# d1.net
KiCad netlist of a schematic drawn in EAGLE
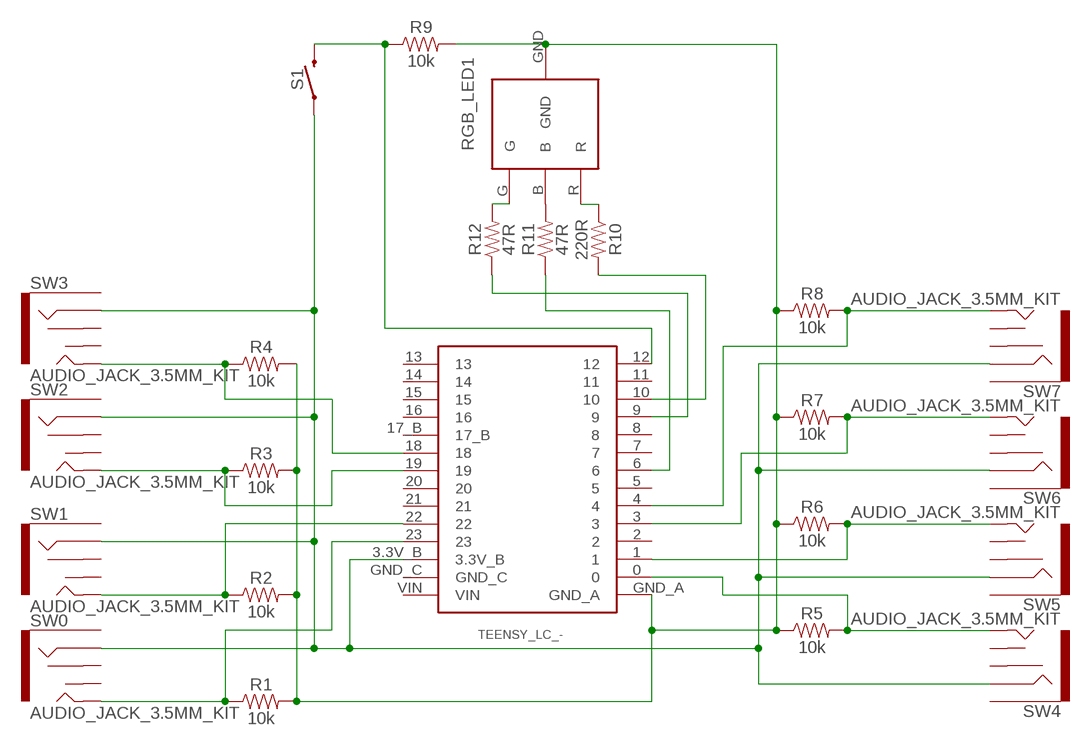
[diagram p0: schematic, sheet 1]

(export (version "E")
  (design (tool "Eeschema 10.0.6"))
  (components
    (comp (ref "R1")
      (value "10k")
      (footprint "eagle-import:AXIAL-0.3-KIT")
      (libsource (lib "eagle-import") (part "10KOHM-HORIZ_KIT-1/4W-1%"))
    )
    (comp (ref "R2")
      (value "10k")
      (footprint "eagle-import:AXIAL-0.3-KIT")
      (libsource (lib "eagle-import") (part "10KOHM-HORIZ_KIT-1/4W-1%"))
    )
    (comp (ref "R3")
      (value "10k")
      (footprint "eagle-import:AXIAL-0.3-KIT")
      (libsource (lib "eagle-import") (part "10KOHM-HORIZ_KIT-1/4W-1%"))
    )
    (comp (ref "R4")
      (value "10k")
      (footprint "eagle-import:AXIAL-0.3-KIT")
      (libsource (lib "eagle-import") (part "10KOHM-HORIZ_KIT-1/4W-1%"))
    )
    (comp (ref "R5")
      (value "10k")
      (footprint "eagle-import:AXIAL-0.3-KIT")
      (libsource (lib "eagle-import") (part "10KOHM-HORIZ_KIT-1/4W-1%"))
    )
    (comp (ref "R6")
      (value "10k")
      (footprint "eagle-import:AXIAL-0.3-KIT")
      (libsource (lib "eagle-import") (part "10KOHM-HORIZ_KIT-1/4W-1%"))
    )
    (comp (ref "R7")
      (value "10k")
      (footprint "eagle-import:AXIAL-0.3-KIT")
      (libsource (lib "eagle-import") (part "10KOHM-HORIZ_KIT-1/4W-1%"))
    )
    (comp (ref "R8")
      (value "10k")
      (footprint "eagle-import:AXIAL-0.3-KIT")
      (libsource (lib "eagle-import") (part "10KOHM-HORIZ_KIT-1/4W-1%"))
    )
    (comp (ref "R9")
      (value "10k")
      (footprint "eagle-import:AXIAL-0.3-KIT")
      (libsource (lib "eagle-import") (part "10KOHM-HORIZ_KIT-1/4W-1%"))
    )
    (comp (ref "R10")
      (value "220R")
      (footprint "eagle-import:AXIAL-0.3-KIT")
      (libsource (lib "eagle-import") (part "10KOHM-HORIZ_KIT-1/4W-1%"))
    )
    (comp (ref "R11")
      (value "47R")
      (footprint "eagle-import:AXIAL-0.3-KIT")
      (libsource (lib "eagle-import") (part "10KOHM-HORIZ_KIT-1/4W-1%"))
    )
    (comp (ref "R12")
      (value "47R")
      (footprint "eagle-import:AXIAL-0.3-KIT")
      (libsource (lib "eagle-import") (part "10KOHM-HORIZ_KIT-1/4W-1%"))
    )
    (comp (ref "RGB_LED1")
      (value "RGB_LED_THRU")
      (footprint "eagle-import:RGB_LEB_RGB_2")
      (libsource (lib "eagle-import") (part "RGB_LED_THRU"))
    )
    (comp (ref "S1")
      (value "MOMENTARY-SWITCH-SPST-PTH-6.0MM")
      (footprint "eagle-import:TACTILE_SWITCH_PTH_6.0MM")
      (libsource (lib "eagle-import") (part "MOMENTARY-SWITCH-SPST-PTH-6.0MM"))
    )
    (comp (ref "SW0")
      (value "AUDIO_JACK_3.5MM_KIT")
      (footprint "eagle-import:AUDIO-JACK-KIT")
      (libsource (lib "eagle-import") (part "AUDIO_JACK_3.5MM_KIT"))
    )
    (comp (ref "SW1")
      (value "AUDIO_JACK_3.5MM_KIT")
      (footprint "eagle-import:AUDIO-JACK-KIT")
      (libsource (lib "eagle-import") (part "AUDIO_JACK_3.5MM_KIT"))
    )
    (comp (ref "SW2")
      (value "AUDIO_JACK_3.5MM_KIT")
      (footprint "eagle-import:AUDIO-JACK-KIT")
      (libsource (lib "eagle-import") (part "AUDIO_JACK_3.5MM_KIT"))
    )
    (comp (ref "SW3")
      (value "AUDIO_JACK_3.5MM_KIT")
      (footprint "eagle-import:AUDIO-JACK-KIT")
      (libsource (lib "eagle-import") (part "AUDIO_JACK_3.5MM_KIT"))
    )
    (comp (ref "SW4")
      (value "AUDIO_JACK_3.5MM_KIT")
      (footprint "eagle-import:AUDIO-JACK-KIT")
      (libsource (lib "eagle-import") (part "AUDIO_JACK_3.5MM_KIT"))
    )
    (comp (ref "SW5")
      (value "AUDIO_JACK_3.5MM_KIT")
      (footprint "eagle-import:AUDIO-JACK-KIT")
      (libsource (lib "eagle-import") (part "AUDIO_JACK_3.5MM_KIT"))
    )
    (comp (ref "SW6")
      (value "AUDIO_JACK_3.5MM_KIT")
      (footprint "eagle-import:AUDIO-JACK-KIT")
      (libsource (lib "eagle-import") (part "AUDIO_JACK_3.5MM_KIT"))
    )
    (comp (ref "SW7")
      (value "AUDIO_JACK_3.5MM_KIT")
      (footprint "eagle-import:AUDIO-JACK-KIT")
      (libsource (lib "eagle-import") (part "AUDIO_JACK_3.5MM_KIT"))
    )
    (comp (ref "U$1")
      (value "TEENSY_LC_-")
      (footprint "eagle-import:TEENSY_LC_-")
      (libsource (lib "eagle-import") (part "TEENSY_LC_-"))
    )
  )
  (nets
    (net (code "1") (name "Net-(R1-1)") (class "Default")
      (node (ref "R1") (pin "P$1") (pinfunction "1_P$1") (pintype "passive"))
      (node (ref "SW0") (pin "TIP") (pinfunction "TIP_TIP") (pintype "bidirectional"))
      (node (ref "U$1") (pin "23") (pinfunction "23_23") (pintype "bidirectional"))
    )
    (net (code "2") (name "Net-(R1-2)") (class "Default")
      (node (ref "R1") (pin "P$2") (pinfunction "2_P$2") (pintype "passive"))
      (node (ref "R2") (pin "P$2") (pinfunction "2_P$2") (pintype "passive"))
      (node (ref "R3") (pin "P$2") (pinfunction "2_P$2") (pintype "passive"))
      (node (ref "R4") (pin "P$2") (pinfunction "2_P$2") (pintype "passive"))
      (node (ref "R5") (pin "P$1") (pinfunction "1_P$1") (pintype "passive"))
      (node (ref "R6") (pin "P$1") (pinfunction "1_P$1") (pintype "passive"))
      (node (ref "R7") (pin "P$1") (pinfunction "1_P$1") (pintype "passive"))
      (node (ref "R8") (pin "P$1") (pinfunction "1_P$1") (pintype "passive"))
      (node (ref "R9") (pin "P$2") (pinfunction "2_P$2") (pintype "passive"))
      (node (ref "RGB_LED1") (pin "GND") (pinfunction "GND_GND") (pintype "bidirectional"))
      (node (ref "U$1") (pin "GND_A") (pinfunction "GND_A_GND_A") (pintype "bidirectional"))
    )
    (net (code "3") (name "Net-(R2-1)") (class "Default")
      (node (ref "R2") (pin "P$1") (pinfunction "1_P$1") (pintype "passive"))
      (node (ref "SW1") (pin "TIP") (pinfunction "TIP_TIP") (pintype "bidirectional"))
      (node (ref "U$1") (pin "22") (pinfunction "22_22") (pintype "bidirectional"))
    )
    (net (code "4") (name "Net-(R3-1)") (class "Default")
      (node (ref "R3") (pin "P$1") (pinfunction "1_P$1") (pintype "passive"))
      (node (ref "SW2") (pin "TIP") (pinfunction "TIP_TIP") (pintype "bidirectional"))
      (node (ref "U$1") (pin "19") (pinfunction "19_19") (pintype "bidirectional"))
    )
    (net (code "5") (name "Net-(R4-1)") (class "Default")
      (node (ref "R4") (pin "P$1") (pinfunction "1_P$1") (pintype "passive"))
      (node (ref "SW3") (pin "TIP") (pinfunction "TIP_TIP") (pintype "bidirectional"))
      (node (ref "U$1") (pin "18") (pinfunction "18_18") (pintype "bidirectional"))
    )
    (net (code "6") (name "Net-(R5-2)") (class "Default")
      (node (ref "R5") (pin "P$2") (pinfunction "2_P$2") (pintype "passive"))
      (node (ref "SW4") (pin "TIP") (pinfunction "TIP_TIP") (pintype "bidirectional"))
      (node (ref "U$1") (pin "0") (pinfunction "0_0") (pintype "bidirectional"))
    )
    (net (code "7") (name "Net-(R6-2)") (class "Default")
      (node (ref "R6") (pin "P$2") (pinfunction "2_P$2") (pintype "passive"))
      (node (ref "SW5") (pin "TIP") (pinfunction "TIP_TIP") (pintype "bidirectional"))
      (node (ref "U$1") (pin "1") (pinfunction "1_1") (pintype "bidirectional"))
    )
    (net (code "8") (name "Net-(R7-2)") (class "Default")
      (node (ref "R7") (pin "P$2") (pinfunction "2_P$2") (pintype "passive"))
      (node (ref "SW6") (pin "TIP") (pinfunction "TIP_TIP") (pintype "bidirectional"))
      (node (ref "U$1") (pin "3") (pinfunction "3_3") (pintype "bidirectional"))
    )
    (net (code "9") (name "Net-(R8-2)") (class "Default")
      (node (ref "R8") (pin "P$2") (pinfunction "2_P$2") (pintype "passive"))
      (node (ref "SW7") (pin "TIP") (pinfunction "TIP_TIP") (pintype "bidirectional"))
      (node (ref "U$1") (pin "4") (pinfunction "4_4") (pintype "bidirectional"))
    )
    (net (code "10") (name "Net-(R9-1)") (class "Default")
      (node (ref "R9") (pin "P$1") (pinfunction "1_P$1") (pintype "passive"))
      (node (ref "S1") (pin "3") (pinfunction "2_3") (pintype "passive"))
      (node (ref "U$1") (pin "12") (pinfunction "12_12") (pintype "bidirectional"))
    )
    (net (code "11") (name "Net-(R10-1)") (class "Default")
      (node (ref "R10") (pin "P$1") (pinfunction "1_P$1") (pintype "passive"))
      (node (ref "RGB_LED1") (pin "R") (pinfunction "R_R") (pintype "bidirectional"))
    )
    (net (code "12") (name "Net-(R10-2)") (class "Default")
      (node (ref "R10") (pin "P$2") (pinfunction "2_P$2") (pintype "passive"))
      (node (ref "U$1") (pin "10") (pinfunction "10_10") (pintype "bidirectional"))
    )
    (net (code "13") (name "Net-(R11-1)") (class "Default")
      (node (ref "R11") (pin "P$1") (pinfunction "1_P$1") (pintype "passive"))
      (node (ref "U$1") (pin "6") (pinfunction "6_6") (pintype "bidirectional"))
    )
    (net (code "14") (name "Net-(R11-2)") (class "Default")
      (node (ref "R11") (pin "P$2") (pinfunction "2_P$2") (pintype "passive"))
      (node (ref "RGB_LED1") (pin "B") (pinfunction "B_B") (pintype "bidirectional"))
    )
    (net (code "15") (name "Net-(R12-1)") (class "Default")
      (node (ref "R12") (pin "P$1") (pinfunction "1_P$1") (pintype "passive"))
      (node (ref "U$1") (pin "9") (pinfunction "9_9") (pintype "bidirectional"))
    )
    (net (code "16") (name "Net-(R12-2)") (class "Default")
      (node (ref "R12") (pin "P$2") (pinfunction "2_P$2") (pintype "passive"))
      (node (ref "RGB_LED1") (pin "G") (pinfunction "G_G") (pintype "bidirectional"))
    )
    (net (code "17") (name "Net-(S1-Pad1)") (class "Default")
      (node (ref "S1") (pin "1") (pinfunction "1_1") (pintype "passive"))
      (node (ref "SW0") (pin "RING") (pinfunction "RING_RING") (pintype "bidirectional"))
      (node (ref "SW1") (pin "RING") (pinfunction "RING_RING") (pintype "bidirectional"))
      (node (ref "SW2") (pin "RING") (pinfunction "RING_RING") (pintype "bidirectional"))
      (node (ref "SW3") (pin "RING") (pinfunction "RING_RING") (pintype "bidirectional"))
      (node (ref "SW4") (pin "RING") (pinfunction "RING_RING") (pintype "bidirectional"))
      (node (ref "SW5") (pin "RING") (pinfunction "RING_RING") (pintype "bidirectional"))
      (node (ref "SW6") (pin "RING") (pinfunction "RING_RING") (pintype "bidirectional"))
      (node (ref "SW7") (pin "RING") (pinfunction "RING_RING") (pintype "bidirectional"))
      (node (ref "U$1") (pin "3.3V_B") (pinfunction "3.3V_B_3.3V_B") (pintype "bidirectional"))
    )
    (net (code "18") (name "unconnected-(SW0-PadRSH)") (class "Default")
      (node (ref "SW0") (pin "RSH") (pinfunction "RSH_RSH") (pintype "bidirectional"))
    )
    (net (code "19") (name "unconnected-(SW0-PadSLEEVE)") (class "Default")
      (node (ref "SW0") (pin "SLEEVE") (pinfunction "SLEEVE_SLEEVE") (pintype "bidirectional"))
    )
    (net (code "20") (name "unconnected-(SW0-PadTSH)") (class "Default")
      (node (ref "SW0") (pin "TSH") (pinfunction "TSH_TSH") (pintype "bidirectional"))
    )
    (net (code "21") (name "unconnected-(SW1-PadRSH)") (class "Default")
      (node (ref "SW1") (pin "RSH") (pinfunction "RSH_RSH") (pintype "bidirectional"))
    )
    (net (code "22") (name "unconnected-(SW1-PadSLEEVE)") (class "Default")
      (node (ref "SW1") (pin "SLEEVE") (pinfunction "SLEEVE_SLEEVE") (pintype "bidirectional"))
    )
    (net (code "23") (name "unconnected-(SW1-PadTSH)") (class "Default")
      (node (ref "SW1") (pin "TSH") (pinfunction "TSH_TSH") (pintype "bidirectional"))
    )
    (net (code "24") (name "unconnected-(SW2-PadRSH)") (class "Default")
      (node (ref "SW2") (pin "RSH") (pinfunction "RSH_RSH") (pintype "bidirectional"))
    )
    (net (code "25") (name "unconnected-(SW2-PadSLEEVE)") (class "Default")
      (node (ref "SW2") (pin "SLEEVE") (pinfunction "SLEEVE_SLEEVE") (pintype "bidirectional"))
    )
    (net (code "26") (name "unconnected-(SW2-PadTSH)") (class "Default")
      (node (ref "SW2") (pin "TSH") (pinfunction "TSH_TSH") (pintype "bidirectional"))
    )
    (net (code "27") (name "unconnected-(SW3-PadRSH)") (class "Default")
      (node (ref "SW3") (pin "RSH") (pinfunction "RSH_RSH") (pintype "bidirectional"))
    )
    (net (code "28") (name "unconnected-(SW3-PadSLEEVE)") (class "Default")
      (node (ref "SW3") (pin "SLEEVE") (pinfunction "SLEEVE_SLEEVE") (pintype "bidirectional"))
    )
    (net (code "29") (name "unconnected-(SW3-PadTSH)") (class "Default")
      (node (ref "SW3") (pin "TSH") (pinfunction "TSH_TSH") (pintype "bidirectional"))
    )
    (net (code "30") (name "unconnected-(SW4-PadRSH)") (class "Default")
      (node (ref "SW4") (pin "RSH") (pinfunction "RSH_RSH") (pintype "bidirectional"))
    )
    (net (code "31") (name "unconnected-(SW4-PadSLEEVE)") (class "Default")
      (node (ref "SW4") (pin "SLEEVE") (pinfunction "SLEEVE_SLEEVE") (pintype "bidirectional"))
    )
    (net (code "32") (name "unconnected-(SW4-PadTSH)") (class "Default")
      (node (ref "SW4") (pin "TSH") (pinfunction "TSH_TSH") (pintype "bidirectional"))
    )
    (net (code "33") (name "unconnected-(SW5-PadRSH)") (class "Default")
      (node (ref "SW5") (pin "RSH") (pinfunction "RSH_RSH") (pintype "bidirectional"))
    )
    (net (code "34") (name "unconnected-(SW5-PadSLEEVE)") (class "Default")
      (node (ref "SW5") (pin "SLEEVE") (pinfunction "SLEEVE_SLEEVE") (pintype "bidirectional"))
    )
    (net (code "35") (name "unconnected-(SW5-PadTSH)") (class "Default")
      (node (ref "SW5") (pin "TSH") (pinfunction "TSH_TSH") (pintype "bidirectional"))
    )
    (net (code "36") (name "unconnected-(SW6-PadRSH)") (class "Default")
      (node (ref "SW6") (pin "RSH") (pinfunction "RSH_RSH") (pintype "bidirectional"))
    )
    (net (code "37") (name "unconnected-(SW6-PadSLEEVE)") (class "Default")
      (node (ref "SW6") (pin "SLEEVE") (pinfunction "SLEEVE_SLEEVE") (pintype "bidirectional"))
    )
    (net (code "38") (name "unconnected-(SW6-PadTSH)") (class "Default")
      (node (ref "SW6") (pin "TSH") (pinfunction "TSH_TSH") (pintype "bidirectional"))
    )
    (net (code "39") (name "unconnected-(SW7-PadRSH)") (class "Default")
      (node (ref "SW7") (pin "RSH") (pinfunction "RSH_RSH") (pintype "bidirectional"))
    )
    (net (code "40") (name "unconnected-(SW7-PadSLEEVE)") (class "Default")
      (node (ref "SW7") (pin "SLEEVE") (pinfunction "SLEEVE_SLEEVE") (pintype "bidirectional"))
    )
    (net (code "41") (name "unconnected-(SW7-PadTSH)") (class "Default")
      (node (ref "SW7") (pin "TSH") (pinfunction "TSH_TSH") (pintype "bidirectional"))
    )
    (net (code "42") (name "unconnected-(U$1-Pad2)") (class "Default")
      (node (ref "U$1") (pin "2") (pinfunction "2_2") (pintype "bidirectional"))
    )
    (net (code "43") (name "unconnected-(U$1-Pad5)") (class "Default")
      (node (ref "U$1") (pin "5") (pinfunction "5_5") (pintype "bidirectional"))
    )
    (net (code "44") (name "unconnected-(U$1-Pad7)") (class "Default")
      (node (ref "U$1") (pin "7") (pinfunction "7_7") (pintype "bidirectional"))
    )
    (net (code "45") (name "unconnected-(U$1-Pad8)") (class "Default")
      (node (ref "U$1") (pin "8") (pinfunction "8_8") (pintype "bidirectional"))
    )
    (net (code "46") (name "unconnected-(U$1-Pad11)") (class "Default")
      (node (ref "U$1") (pin "11") (pinfunction "11_11") (pintype "bidirectional"))
    )
    (net (code "47") (name "unconnected-(U$1-Pad13)") (class "Default")
      (node (ref "U$1") (pin "13") (pinfunction "13_13") (pintype "bidirectional"))
    )
    (net (code "48") (name "unconnected-(U$1-Pad14)") (class "Default")
      (node (ref "U$1") (pin "14") (pinfunction "14_14") (pintype "bidirectional"))
    )
    (net (code "49") (name "unconnected-(U$1-Pad15)") (class "Default")
      (node (ref "U$1") (pin "15") (pinfunction "15_15") (pintype "bidirectional"))
    )
    (net (code "50") (name "unconnected-(U$1-Pad16)") (class "Default")
      (node (ref "U$1") (pin "16") (pinfunction "16_16") (pintype "bidirectional"))
    )
    (net (code "51") (name "unconnected-(U$1-Pad17_B)") (class "Default")
      (node (ref "U$1") (pin "17_B") (pinfunction "17_B_17_B") (pintype "bidirectional"))
    )
    (net (code "52") (name "unconnected-(U$1-Pad20)") (class "Default")
      (node (ref "U$1") (pin "20") (pinfunction "20_20") (pintype "bidirectional"))
    )
    (net (code "53") (name "unconnected-(U$1-Pad21)") (class "Default")
      (node (ref "U$1") (pin "21") (pinfunction "21_21") (pintype "bidirectional"))
    )
    (net (code "54") (name "unconnected-(U$1-PadGND_C)") (class "Default")
      (node (ref "U$1") (pin "GND_C") (pinfunction "GND_C_GND_C") (pintype "bidirectional"))
    )
    (net (code "55") (name "unconnected-(U$1-PadVIN)") (class "Default")
      (node (ref "U$1") (pin "VIN") (pinfunction "VIN_VIN") (pintype "bidirectional"))
    )
  )
)
